# source_eagle.net
KiCad netlist of a schematic drawn in EAGLE
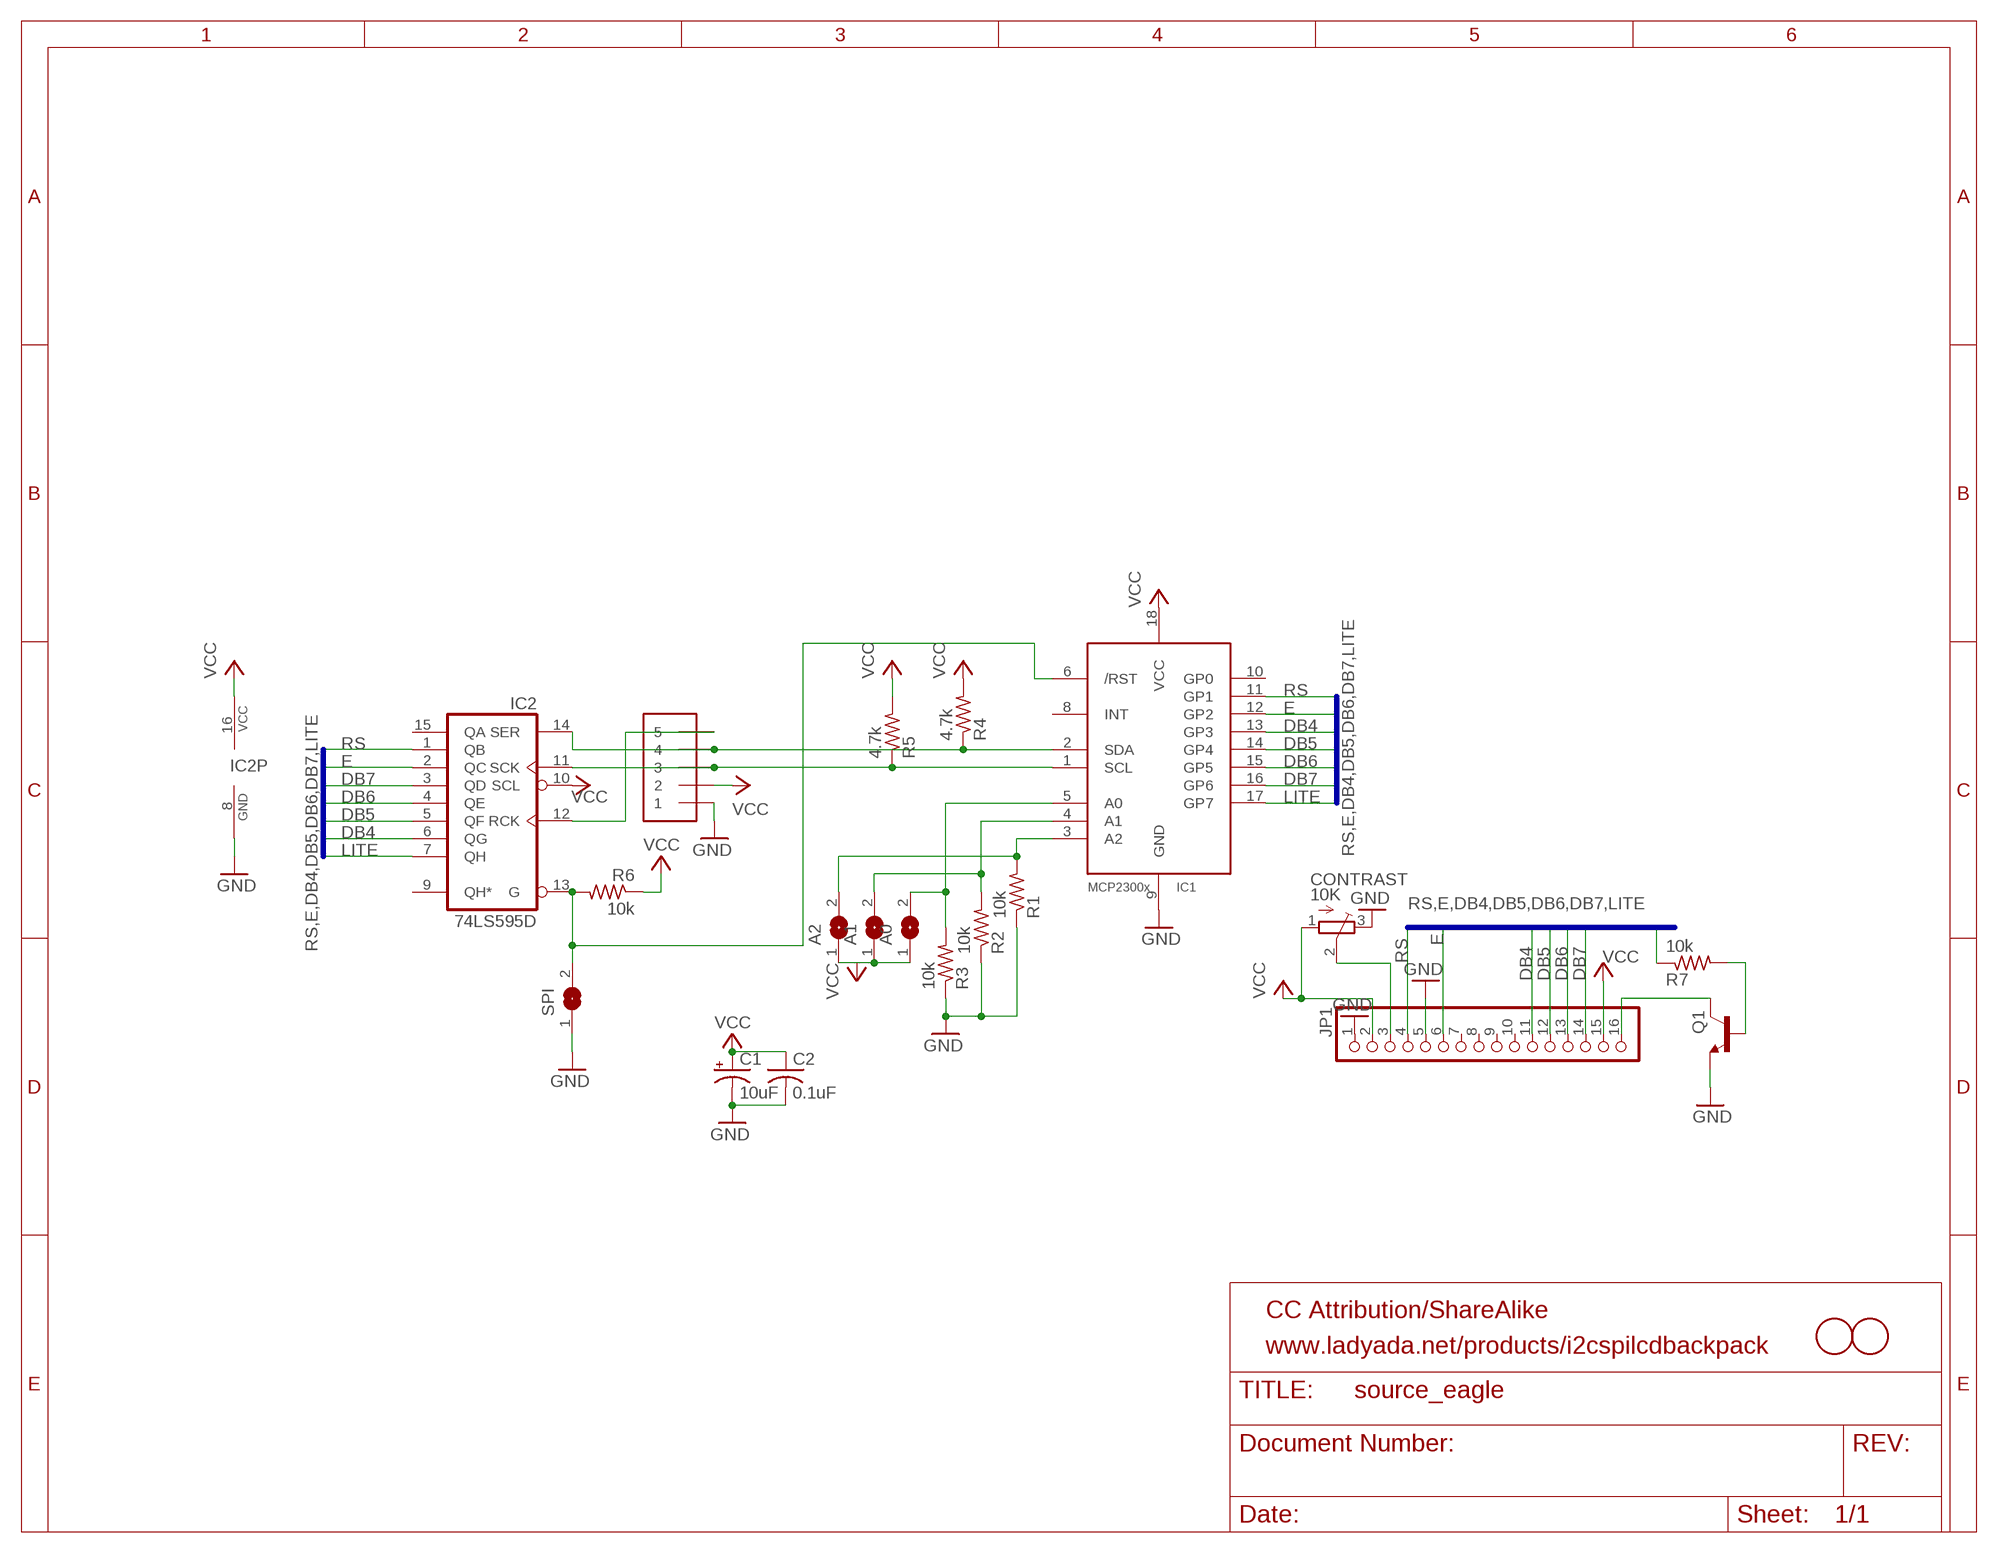
[diagram p0: schematic, sheet 1]

(export (version "E")
  (design (tool "Eeschema 10.0.6"))
  (components
    (comp (ref "A0") (value "SJ") (footprint "eagle-import:SJ") (libsource (lib "eagle-import") (part "SJ")))
    (comp (ref "A1") (value "SJ") (footprint "eagle-import:SJ") (libsource (lib "eagle-import") (part "SJ")))
    (comp (ref "A2") (value "SJ") (footprint "eagle-import:SJ") (libsource (lib "eagle-import") (part "SJ")))
    (comp (ref "C1")
      (value "10uF")
      (footprint "eagle-import:A_3216-18R")
      (libsource (lib "eagle-import") (part "CPOL-USA/3216-18R"))
    )
    (comp (ref "C2")
      (value "0.1uF")
      (footprint "eagle-import:C0805K")
      (libsource (lib "eagle-import") (part "C-USC0805K"))
    )
    (comp (ref "CONTRAST")
      (value "10K")
      (footprint "eagle-import:TC33X")
      (libsource (lib "eagle-import") (part "TRIMPOTTC33X"))
    )
    (comp (ref "IC1")
      (value "MCP2300X/SO")
      (footprint "eagle-import:SO18W")
      (libsource (lib "eagle-import") (part "MCP2300X/SO"))
    )
    (comp (ref "IC2")
      (value "74LS595D")
      (footprint "eagle-import:SO16")
      (libsource (lib "eagle-import") (part "74595DLS"))
    )
    (comp (ref "J1")
      (value "1X5")
      (footprint "eagle-import:3.5MM-5P")
      (libsource (lib "eagle-import") (part "1X5"))
    )
    (comp (ref "JP1")
      (value "PINHD-1X16")
      (footprint "eagle-import:1X16")
      (libsource (lib "eagle-import") (part "PINHD-1X16"))
    )
    (comp (ref "Q1")
      (value "MMBT2222ALT1-NPN-SOT23-BEC")
      (footprint "eagle-import:SOT23-BEC")
      (libsource (lib "eagle-import") (part "-NPN-SOT23-BECMMBT2222ALT1"))
    )
    (comp (ref "R1")
      (value "10k")
      (footprint "eagle-import:R0805")
      (libsource (lib "eagle-import") (part "R-US_R0805"))
    )
    (comp (ref "R2")
      (value "10k")
      (footprint "eagle-import:R0805")
      (libsource (lib "eagle-import") (part "R-US_R0805"))
    )
    (comp (ref "R3")
      (value "10k")
      (footprint "eagle-import:R0805")
      (libsource (lib "eagle-import") (part "R-US_R0805"))
    )
    (comp (ref "R4")
      (value "4.7k")
      (footprint "eagle-import:R0805")
      (libsource (lib "eagle-import") (part "R-US_R0805"))
    )
    (comp (ref "R5")
      (value "4.7k")
      (footprint "eagle-import:R0805")
      (libsource (lib "eagle-import") (part "R-US_R0805"))
    )
    (comp (ref "R6")
      (value "10k")
      (footprint "eagle-import:R0805")
      (libsource (lib "eagle-import") (part "R-US_R0805"))
    )
    (comp (ref "R7")
      (value "10k")
      (footprint "eagle-import:R0805")
      (libsource (lib "eagle-import") (part "R-US_R0805"))
    )
    (comp (ref "SPI") (value "SJ") (footprint "eagle-import:SJ") (libsource (lib "eagle-import") (part "SJ")))
    (comp (ref "U$1")
      (value "FIDUCIAL")
      (footprint "eagle-import:FIDUCIAL_1MM")
      (libsource (lib "eagle-import") (part "FIDUCIAL"))
    )
    (comp (ref "U$2")
      (value "FIDUCIAL")
      (footprint "eagle-import:FIDUCIAL_1MM")
      (libsource (lib "eagle-import") (part "FIDUCIAL"))
    )
  )
  (nets
    (net (code "1") (name "/DB4") (class "Default")
      (node (ref "IC1") (pin "13") (pinfunction "GP3_13") (pintype "bidirectional"))
      (node (ref "IC2") (pin "6") (pinfunction "QG_6") (pintype "tri_state"))
      (node (ref "JP1") (pin "11") (pinfunction "11_11") (pintype "passive"))
    )
    (net (code "2") (name "/DB5") (class "Default")
      (node (ref "IC1") (pin "14") (pinfunction "GP4_14") (pintype "bidirectional"))
      (node (ref "IC2") (pin "5") (pinfunction "QF_5") (pintype "tri_state"))
      (node (ref "JP1") (pin "12") (pinfunction "12_12") (pintype "passive"))
    )
    (net (code "3") (name "/DB6") (class "Default")
      (node (ref "IC1") (pin "15") (pinfunction "GP5_15") (pintype "bidirectional"))
      (node (ref "IC2") (pin "4") (pinfunction "QE_4") (pintype "tri_state"))
      (node (ref "JP1") (pin "13") (pinfunction "13_13") (pintype "passive"))
    )
    (net (code "4") (name "/DB7") (class "Default")
      (node (ref "IC1") (pin "16") (pinfunction "GP6_16") (pintype "bidirectional"))
      (node (ref "IC2") (pin "3") (pinfunction "QD_3") (pintype "tri_state"))
      (node (ref "JP1") (pin "14") (pinfunction "14_14") (pintype "passive"))
    )
    (net (code "5") (name "/E") (class "Default")
      (node (ref "IC1") (pin "12") (pinfunction "GP2_12") (pintype "bidirectional"))
      (node (ref "IC2") (pin "2") (pinfunction "QC_2") (pintype "tri_state"))
      (node (ref "JP1") (pin "6") (pinfunction "6_6") (pintype "passive"))
    )
    (net (code "6") (name "/LITE") (class "Default")
      (node (ref "IC1") (pin "17") (pinfunction "GP7_17") (pintype "bidirectional"))
      (node (ref "IC2") (pin "7") (pinfunction "QH_7") (pintype "tri_state"))
      (node (ref "R7") (pin "1") (pinfunction "1_1") (pintype "passive"))
    )
    (net (code "7") (name "/RS") (class "Default")
      (node (ref "IC1") (pin "11") (pinfunction "GP1_11") (pintype "bidirectional"))
      (node (ref "IC2") (pin "1") (pinfunction "QB_1") (pintype "tri_state"))
      (node (ref "JP1") (pin "4") (pinfunction "4_4") (pintype "passive"))
    )
    (net (code "9") (name "GND") (class "Default")
      (node (ref "C1") (pin "-") (pinfunction "-_-") (pintype "passive"))
      (node (ref "C2") (pin "2") (pinfunction "2_2") (pintype "passive"))
      (node (ref "CONTRAST") (pin "3") (pinfunction "E_3") (pintype "passive"))
      (node (ref "IC1") (pin "9") (pinfunction "GND_9") (pintype "power_in"))
      (node (ref "IC2") (pin "8") (pinfunction "GND_8") (pintype "power_in"))
      (node (ref "J1") (pin "1") (pinfunction "1_1") (pintype "passive"))
      (node (ref "JP1") (pin "1") (pinfunction "1_1") (pintype "passive"))
      (node (ref "JP1") (pin "5") (pinfunction "5_5") (pintype "passive"))
      (node (ref "Q1") (pin "E") (pinfunction "E_E") (pintype "passive"))
      (node (ref "R1") (pin "1") (pinfunction "1_1") (pintype "passive"))
      (node (ref "R2") (pin "1") (pinfunction "1_1") (pintype "passive"))
      (node (ref "R3") (pin "1") (pinfunction "1_1") (pintype "passive"))
      (node (ref "SPI") (pin "1") (pinfunction "1_1") (pintype "passive"))
    )
    (net (code "10") (name "Net-(CONTRAST-S)") (class "Default")
      (node (ref "CONTRAST") (pin "2") (pinfunction "S_2") (pintype "passive"))
      (node (ref "JP1") (pin "3") (pinfunction "3_3") (pintype "passive"))
    )
    (net (code "11") (name "Net-(IC1-A0)") (class "Default")
      (node (ref "A0") (pin "2") (pinfunction "2_2") (pintype "passive"))
      (node (ref "IC1") (pin "5") (pinfunction "A0_5") (pintype "input"))
      (node (ref "R3") (pin "2") (pinfunction "2_2") (pintype "passive"))
    )
    (net (code "12") (name "Net-(IC1-A1)") (class "Default")
      (node (ref "A1") (pin "2") (pinfunction "2_2") (pintype "passive"))
      (node (ref "IC1") (pin "4") (pinfunction "A1_4") (pintype "input"))
      (node (ref "R2") (pin "2") (pinfunction "2_2") (pintype "passive"))
    )
    (net (code "13") (name "Net-(IC1-A2)") (class "Default")
      (node (ref "A2") (pin "2") (pinfunction "2_2") (pintype "passive"))
      (node (ref "IC1") (pin "3") (pinfunction "A2_3") (pintype "input"))
      (node (ref "R1") (pin "2") (pinfunction "2_2") (pintype "passive"))
    )
    (net (code "14") (name "Net-(IC1-SCL)") (class "Default")
      (node (ref "IC1") (pin "1") (pinfunction "SCL_1") (pintype "bidirectional"))
      (node (ref "IC2") (pin "11") (pinfunction "SCK_11") (pintype "input"))
      (node (ref "J1") (pin "3") (pinfunction "3_3") (pintype "passive"))
      (node (ref "R5") (pin "1") (pinfunction "1_1") (pintype "passive"))
    )
    (net (code "15") (name "Net-(IC1-SDA)") (class "Default")
      (node (ref "IC1") (pin "2") (pinfunction "SDA_2") (pintype "bidirectional"))
      (node (ref "IC2") (pin "14") (pinfunction "SER_14") (pintype "input"))
      (node (ref "J1") (pin "4") (pinfunction "4_4") (pintype "passive"))
      (node (ref "R4") (pin "1") (pinfunction "1_1") (pintype "passive"))
    )
    (net (code "16") (name "Net-(IC1-{slash}RST)") (class "Default")
      (node (ref "IC1") (pin "6") (pinfunction "/RST_6") (pintype "input"))
      (node (ref "IC2") (pin "13") (pinfunction "G_13") (pintype "input"))
      (node (ref "R6") (pin "2") (pinfunction "2_2") (pintype "passive"))
      (node (ref "SPI") (pin "2") (pinfunction "2_2") (pintype "passive"))
    )
    (net (code "17") (name "Net-(IC2A-RCK)") (class "Default")
      (node (ref "IC2") (pin "12") (pinfunction "RCK_12") (pintype "input"))
      (node (ref "J1") (pin "5") (pinfunction "5_5") (pintype "passive"))
    )
    (net (code "18") (name "Net-(JP1-Pad16)") (class "Default")
      (node (ref "JP1") (pin "16") (pinfunction "16_16") (pintype "passive"))
      (node (ref "Q1") (pin "C") (pinfunction "C_C") (pintype "passive"))
    )
    (net (code "19") (name "Net-(Q1-PadB)") (class "Default")
      (node (ref "Q1") (pin "B") (pinfunction "B_B") (pintype "passive"))
      (node (ref "R7") (pin "2") (pinfunction "2_2") (pintype "passive"))
    )
    (net (code "20") (name "VCC") (class "Default")
      (node (ref "A0") (pin "1") (pinfunction "1_1") (pintype "passive"))
      (node (ref "A1") (pin "1") (pinfunction "1_1") (pintype "passive"))
      (node (ref "A2") (pin "1") (pinfunction "1_1") (pintype "passive"))
      (node (ref "C1") (pin "+") (pinfunction "+_+") (pintype "passive"))
      (node (ref "C2") (pin "1") (pinfunction "1_1") (pintype "passive"))
      (node (ref "CONTRAST") (pin "1") (pinfunction "A_1") (pintype "passive"))
      (node (ref "IC1") (pin "18") (pinfunction "VCC_18") (pintype "power_in"))
      (node (ref "IC2") (pin "10") (pinfunction "SCL_10") (pintype "input"))
      (node (ref "IC2") (pin "16") (pinfunction "VCC_16") (pintype "power_in"))
      (node (ref "J1") (pin "2") (pinfunction "2_2") (pintype "passive"))
      (node (ref "JP1") (pin "15") (pinfunction "15_15") (pintype "passive"))
      (node (ref "JP1") (pin "2") (pinfunction "2_2") (pintype "passive"))
      (node (ref "R4") (pin "2") (pinfunction "2_2") (pintype "passive"))
      (node (ref "R5") (pin "2") (pinfunction "2_2") (pintype "passive"))
      (node (ref "R6") (pin "1") (pinfunction "1_1") (pintype "passive"))
    )
    (net (code "21") (name "unconnected-(IC1-GP0-Pad10)") (class "Default")
      (node (ref "IC1") (pin "10") (pinfunction "GP0_10") (pintype "bidirectional"))
    )
    (net (code "22") (name "unconnected-(IC1-INT-Pad8)") (class "Default")
      (node (ref "IC1") (pin "8") (pinfunction "INT_8") (pintype "output"))
    )
    (net (code "23") (name "unconnected-(IC2A-QA-Pad15)") (class "Default")
      (node (ref "IC2") (pin "15") (pinfunction "QA_15") (pintype "tri_state"))
    )
    (net (code "24") (name "unconnected-(IC2A-QH*-Pad9)") (class "Default")
      (node (ref "IC2") (pin "9") (pinfunction "QH*_9") (pintype "tri_state"))
    )
    (net (code "25") (name "unconnected-(JP1-Pad7)") (class "Default")
      (node (ref "JP1") (pin "7") (pinfunction "7_7") (pintype "passive"))
    )
    (net (code "26") (name "unconnected-(JP1-Pad8)") (class "Default")
      (node (ref "JP1") (pin "8") (pinfunction "8_8") (pintype "passive"))
    )
    (net (code "27") (name "unconnected-(JP1-Pad9)") (class "Default")
      (node (ref "JP1") (pin "9") (pinfunction "9_9") (pintype "passive"))
    )
    (net (code "28") (name "unconnected-(JP1-Pad10)") (class "Default")
      (node (ref "JP1") (pin "10") (pinfunction "10_10") (pintype "passive"))
    )
  )
)
